# Solenoid_Driver.net
KiCad netlist of a schematic drawn in EAGLE
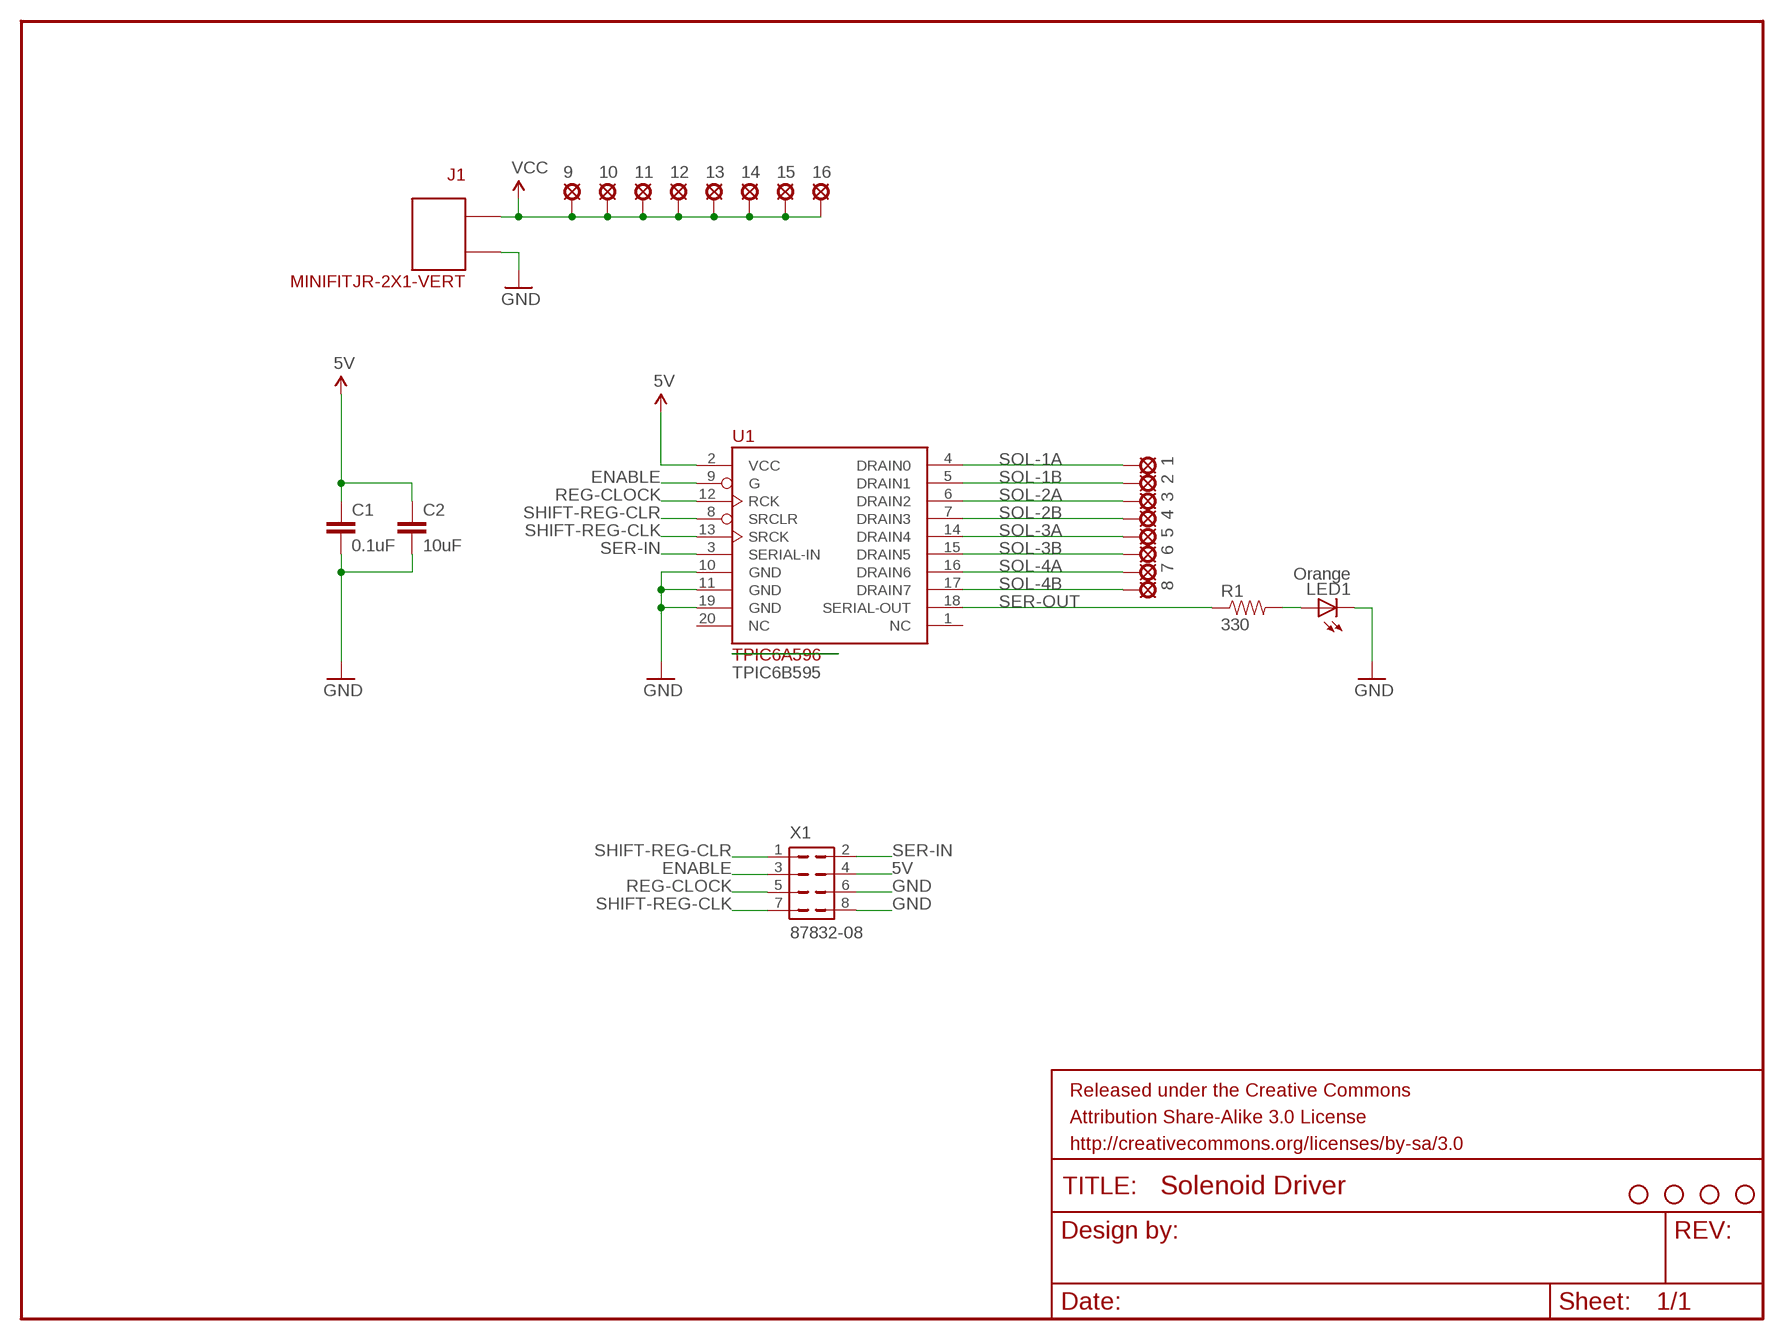
[diagram p0: schematic, sheet 1]

(export (version "E")
  (design (tool "Eeschema 10.0.6"))
  (components
    (comp (ref "1")
      (value "SE14")
      (footprint "eagle-import:SE14")
      (libsource (lib "eagle-import") (part "SE14"))
    )
    (comp (ref "2")
      (value "SE14")
      (footprint "eagle-import:SE14")
      (libsource (lib "eagle-import") (part "SE14"))
    )
    (comp (ref "3")
      (value "SE14")
      (footprint "eagle-import:SE14")
      (libsource (lib "eagle-import") (part "SE14"))
    )
    (comp (ref "4")
      (value "SE14")
      (footprint "eagle-import:SE14")
      (libsource (lib "eagle-import") (part "SE14"))
    )
    (comp (ref "5")
      (value "SE14")
      (footprint "eagle-import:SE14")
      (libsource (lib "eagle-import") (part "SE14"))
    )
    (comp (ref "6")
      (value "SE14")
      (footprint "eagle-import:SE14")
      (libsource (lib "eagle-import") (part "SE14"))
    )
    (comp (ref "7")
      (value "SE14")
      (footprint "eagle-import:SE14")
      (libsource (lib "eagle-import") (part "SE14"))
    )
    (comp (ref "8")
      (value "SE14")
      (footprint "eagle-import:SE14")
      (libsource (lib "eagle-import") (part "SE14"))
    )
    (comp (ref "9")
      (value "SE14")
      (footprint "eagle-import:SE14")
      (libsource (lib "eagle-import") (part "SE14"))
    )
    (comp (ref "10")
      (value "SE14")
      (footprint "eagle-import:SE14")
      (libsource (lib "eagle-import") (part "SE14"))
    )
    (comp (ref "11")
      (value "SE14")
      (footprint "eagle-import:SE14")
      (libsource (lib "eagle-import") (part "SE14"))
    )
    (comp (ref "12")
      (value "SE14")
      (footprint "eagle-import:SE14")
      (libsource (lib "eagle-import") (part "SE14"))
    )
    (comp (ref "13")
      (value "SE14")
      (footprint "eagle-import:SE14")
      (libsource (lib "eagle-import") (part "SE14"))
    )
    (comp (ref "14")
      (value "SE14")
      (footprint "eagle-import:SE14")
      (libsource (lib "eagle-import") (part "SE14"))
    )
    (comp (ref "15")
      (value "SE14")
      (footprint "eagle-import:SE14")
      (libsource (lib "eagle-import") (part "SE14"))
    )
    (comp (ref "16")
      (value "SE14")
      (footprint "eagle-import:SE14")
      (libsource (lib "eagle-import") (part "SE14"))
    )
    (comp (ref "C1")
      (value "0.1uF")
      (footprint "eagle-import:0603-CAP")
      (libsource (lib "eagle-import") (part "CAP0603-CAP"))
    )
    (comp (ref "C2")
      (value "10uF")
      (footprint "eagle-import:0603-CAP")
      (libsource (lib "eagle-import") (part "CAP0603-CAP"))
    )
    (comp (ref "J1")
      (value "MINIFITJR-2X1-VERT")
      (footprint "eagle-import:5566-02B")
      (libsource (lib "eagle-import") (part "MINIFITJR-2X1-VERT"))
    )
    (comp (ref "JP1")
      (value "STAND-OFF")
      (footprint "eagle-import:STAND-OFF")
      (libsource (lib "eagle-import") (part "STAND-OFF"))
    )
    (comp (ref "JP2")
      (value "STAND-OFF")
      (footprint "eagle-import:STAND-OFF")
      (libsource (lib "eagle-import") (part "STAND-OFF"))
    )
    (comp (ref "JP3")
      (value "STAND-OFF")
      (footprint "eagle-import:STAND-OFF")
      (libsource (lib "eagle-import") (part "STAND-OFF"))
    )
    (comp (ref "JP4")
      (value "STAND-OFF")
      (footprint "eagle-import:STAND-OFF")
      (libsource (lib "eagle-import") (part "STAND-OFF"))
    )
    (comp (ref "LED1")
      (value "Orange")
      (footprint "eagle-import:LED-0603")
      (libsource (lib "eagle-import") (part "LED0603"))
    )
    (comp (ref "R1")
      (value "330")
      (footprint "eagle-import:0603-RES")
      (libsource (lib "eagle-import") (part "RESISTOR0603-RES"))
    )
    (comp (ref "U1")
      (value "TPIC6A596")
      (footprint "eagle-import:SOIC20-W")
      (libsource (lib "eagle-import") (part "TPIC6A596"))
    )
    (comp (ref "X1")
      (value "87832-08")
      (footprint "eagle-import:87832-08")
      (libsource (lib "eagle-import") (part "87832-08"))
    )
  )
  (nets
    (net (code "1") (name "/ENABLE") (class "Default")
      (node (ref "U1") (pin "9") (pinfunction "G_9") (pintype "bidirectional"))
      (node (ref "X1") (pin "3") (pinfunction "3_3") (pintype "passive"))
    )
    (net (code "2") (name "/REG-CLOCK") (class "Default")
      (node (ref "U1") (pin "12") (pinfunction "RCK_12") (pintype "bidirectional"))
      (node (ref "X1") (pin "5") (pinfunction "5_5") (pintype "passive"))
    )
    (net (code "3") (name "/SER-IN") (class "Default")
      (node (ref "U1") (pin "3") (pinfunction "SERIAL-IN_3") (pintype "bidirectional"))
      (node (ref "X1") (pin "2") (pinfunction "2_2") (pintype "passive"))
    )
    (net (code "4") (name "/SER-OUT") (class "Default")
      (node (ref "R1") (pin "1") (pinfunction "1_1") (pintype "passive"))
      (node (ref "U1") (pin "18") (pinfunction "SERIAL-OUT_18") (pintype "bidirectional"))
    )
    (net (code "5") (name "/SHIFT-REG-CLK") (class "Default")
      (node (ref "U1") (pin "13") (pinfunction "SRCK_13") (pintype "bidirectional"))
      (node (ref "X1") (pin "7") (pinfunction "7_7") (pintype "passive"))
    )
    (net (code "6") (name "/SHIFT-REG-CLR") (class "Default")
      (node (ref "U1") (pin "8") (pinfunction "SRCLR_8") (pintype "bidirectional"))
      (node (ref "X1") (pin "1") (pinfunction "1_1") (pintype "passive"))
    )
    (net (code "7") (name "/SOL-1A") (class "Default")
      (node (ref "1") (pin "MP") (pinfunction "MP_MP") (pintype "passive"))
      (node (ref "U1") (pin "4") (pinfunction "DRAIN0_4") (pintype "bidirectional"))
    )
    (net (code "8") (name "/SOL-1B") (class "Default")
      (node (ref "2") (pin "MP") (pinfunction "MP_MP") (pintype "passive"))
      (node (ref "U1") (pin "5") (pinfunction "DRAIN1_5") (pintype "bidirectional"))
    )
    (net (code "9") (name "/SOL-2A") (class "Default")
      (node (ref "3") (pin "MP") (pinfunction "MP_MP") (pintype "passive"))
      (node (ref "U1") (pin "6") (pinfunction "DRAIN2_6") (pintype "bidirectional"))
    )
    (net (code "10") (name "/SOL-2B") (class "Default")
      (node (ref "4") (pin "MP") (pinfunction "MP_MP") (pintype "passive"))
      (node (ref "U1") (pin "7") (pinfunction "DRAIN3_7") (pintype "bidirectional"))
    )
    (net (code "11") (name "/SOL-3A") (class "Default")
      (node (ref "5") (pin "MP") (pinfunction "MP_MP") (pintype "passive"))
      (node (ref "U1") (pin "14") (pinfunction "DRAIN4_14") (pintype "bidirectional"))
    )
    (net (code "12") (name "/SOL-3B") (class "Default")
      (node (ref "6") (pin "MP") (pinfunction "MP_MP") (pintype "passive"))
      (node (ref "U1") (pin "15") (pinfunction "DRAIN5_15") (pintype "bidirectional"))
    )
    (net (code "13") (name "/SOL-4A") (class "Default")
      (node (ref "7") (pin "MP") (pinfunction "MP_MP") (pintype "passive"))
      (node (ref "U1") (pin "16") (pinfunction "DRAIN6_16") (pintype "bidirectional"))
    )
    (net (code "14") (name "/SOL-4B") (class "Default")
      (node (ref "8") (pin "MP") (pinfunction "MP_MP") (pintype "passive"))
      (node (ref "U1") (pin "17") (pinfunction "DRAIN7_17") (pintype "bidirectional"))
    )
    (net (code "15") (name "5V") (class "Default")
      (node (ref "C1") (pin "1") (pinfunction "1_1") (pintype "passive"))
      (node (ref "C2") (pin "1") (pinfunction "1_1") (pintype "passive"))
      (node (ref "U1") (pin "2") (pinfunction "VCC_2") (pintype "bidirectional"))
      (node (ref "X1") (pin "4") (pinfunction "4_4") (pintype "passive"))
    )
    (net (code "16") (name "GND") (class "Default")
      (node (ref "C1") (pin "2") (pinfunction "2_2") (pintype "passive"))
      (node (ref "C2") (pin "2") (pinfunction "2_2") (pintype "passive"))
      (node (ref "J1") (pin "P$2") (pinfunction "P$2_P$2") (pintype "bidirectional"))
      (node (ref "LED1") (pin "C") (pinfunction "C_C") (pintype "passive"))
      (node (ref "U1") (pin "10") (pinfunction "GND_10") (pintype "bidirectional"))
      (node (ref "U1") (pin "11") (pinfunction "GND_11") (pintype "bidirectional"))
      (node (ref "U1") (pin "19") (pinfunction "GND_19") (pintype "bidirectional"))
      (node (ref "X1") (pin "6") (pinfunction "6_6") (pintype "passive"))
      (node (ref "X1") (pin "8") (pinfunction "8_8") (pintype "passive"))
    )
    (net (code "17") (name "Net-(LED1-PadA)") (class "Default")
      (node (ref "LED1") (pin "A") (pinfunction "A_A") (pintype "passive"))
      (node (ref "R1") (pin "2") (pinfunction "2_2") (pintype "passive"))
    )
    (net (code "18") (name "VCC") (class "Default")
      (node (ref "10") (pin "MP") (pinfunction "MP_MP") (pintype "passive"))
      (node (ref "11") (pin "MP") (pinfunction "MP_MP") (pintype "passive"))
      (node (ref "12") (pin "MP") (pinfunction "MP_MP") (pintype "passive"))
      (node (ref "13") (pin "MP") (pinfunction "MP_MP") (pintype "passive"))
      (node (ref "14") (pin "MP") (pinfunction "MP_MP") (pintype "passive"))
      (node (ref "15") (pin "MP") (pinfunction "MP_MP") (pintype "passive"))
      (node (ref "16") (pin "MP") (pinfunction "MP_MP") (pintype "passive"))
      (node (ref "9") (pin "MP") (pinfunction "MP_MP") (pintype "passive"))
      (node (ref "J1") (pin "P$1") (pinfunction "P$1_P$1") (pintype "bidirectional"))
    )
    (net (code "19") (name "unconnected-(U1-NC-Pad1)") (class "Default")
      (node (ref "U1") (pin "1") (pinfunction "NC_1") (pintype "bidirectional"))
    )
    (net (code "20") (name "unconnected-(U1-NC-Pad20)") (class "Default")
      (node (ref "U1") (pin "20") (pinfunction "NC_20") (pintype "bidirectional"))
    )
  )
)
